# Random_Bit_Module.net
KiCad netlist of a schematic drawn in EAGLE
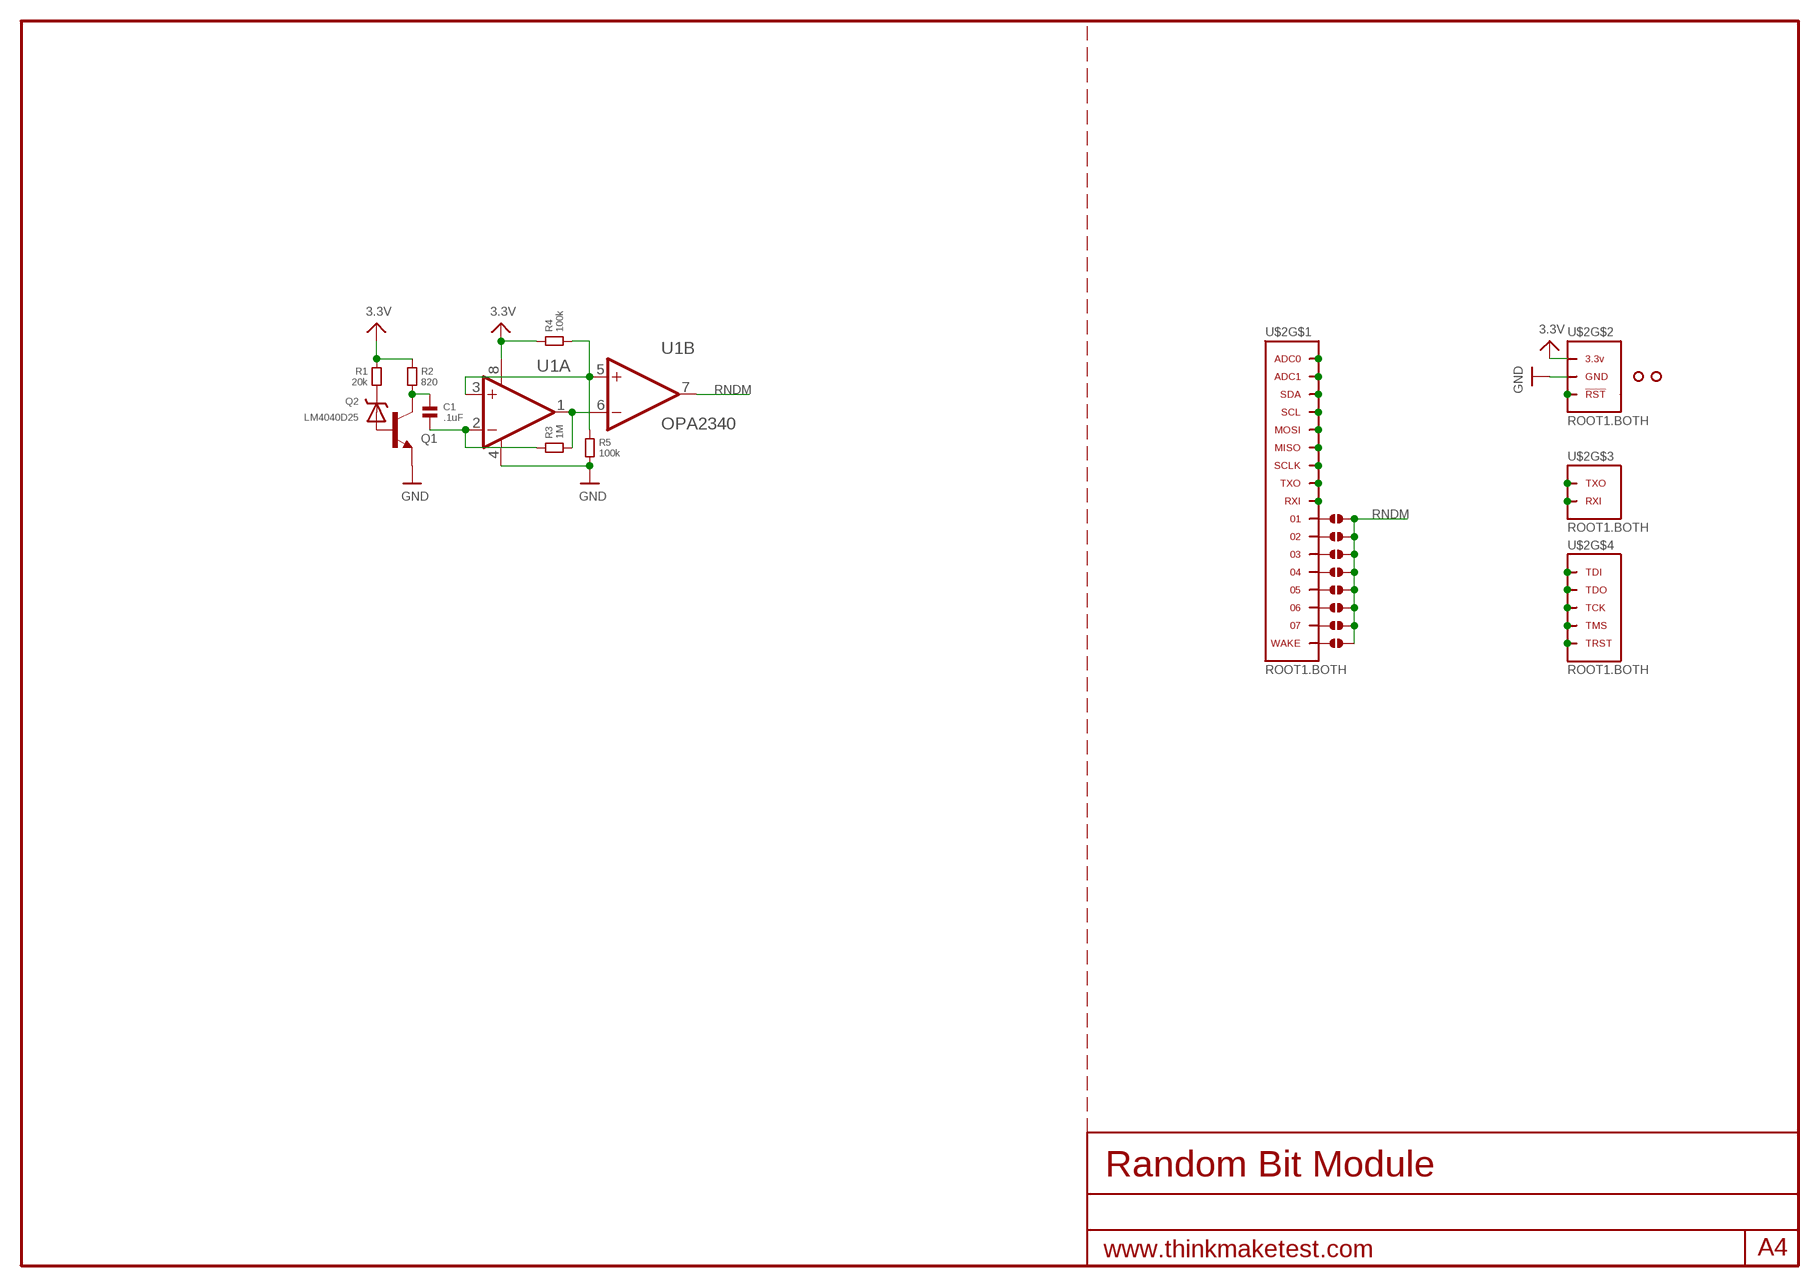
[diagram p0: schematic, sheet 1]

(export (version "E")
  (design (tool "Eeschema 10.0.6"))
  (components
    (comp (ref "C1")
      (value ".1uF")
      (footprint "eagle-import:0603")
      (libsource (lib "eagle-import") (part "CAPACITOR.0603"))
    )
    (comp (ref "J1")
      (value "SOLDERJUMPER.2.SML")
      (footprint "eagle-import:2.SML")
      (libsource (lib "eagle-import") (part "SOLDERJUMPER.2.SML"))
    )
    (comp (ref "J2")
      (value "SOLDERJUMPER.2.SML")
      (footprint "eagle-import:2.SML")
      (libsource (lib "eagle-import") (part "SOLDERJUMPER.2.SML"))
    )
    (comp (ref "J3")
      (value "SOLDERJUMPER.2.SML")
      (footprint "eagle-import:2.SML")
      (libsource (lib "eagle-import") (part "SOLDERJUMPER.2.SML"))
    )
    (comp (ref "J4")
      (value "SOLDERJUMPER.2.SML")
      (footprint "eagle-import:2.SML")
      (libsource (lib "eagle-import") (part "SOLDERJUMPER.2.SML"))
    )
    (comp (ref "J5")
      (value "SOLDERJUMPER.2.SML")
      (footprint "eagle-import:2.SML")
      (libsource (lib "eagle-import") (part "SOLDERJUMPER.2.SML"))
    )
    (comp (ref "J6")
      (value "SOLDERJUMPER.2.SML")
      (footprint "eagle-import:2.SML")
      (libsource (lib "eagle-import") (part "SOLDERJUMPER.2.SML"))
    )
    (comp (ref "J7")
      (value "SOLDERJUMPER.2.SML")
      (footprint "eagle-import:2.SML")
      (libsource (lib "eagle-import") (part "SOLDERJUMPER.2.SML"))
    )
    (comp (ref "J8")
      (value "SOLDERJUMPER.2.SML")
      (footprint "eagle-import:2.SML")
      (libsource (lib "eagle-import") (part "SOLDERJUMPER.2.SML"))
    )
    (comp (ref "Q1")
      (value "TRANSISTOR_NPN")
      (footprint "eagle-import:SOT23-R")
      (libsource (lib "eagle-import") (part "TRANSISTOR_NPN"))
    )
    (comp (ref "Q2")
      (value "LM4040D25")
      (footprint "eagle-import:SOT23-3")
      (libsource (lib "eagle-import") (part "V-REFERENCESMD"))
    )
    (comp (ref "R1")
      (value "20k")
      (footprint "eagle-import:0603")
      (libsource (lib "eagle-import") (part "RESISTOR.0603"))
    )
    (comp (ref "R2")
      (value "820")
      (footprint "eagle-import:0603")
      (libsource (lib "eagle-import") (part "RESISTOR.0603"))
    )
    (comp (ref "R3")
      (value "1M")
      (footprint "eagle-import:0603")
      (libsource (lib "eagle-import") (part "RESISTOR.0603"))
    )
    (comp (ref "R4")
      (value "100k")
      (footprint "eagle-import:0603")
      (libsource (lib "eagle-import") (part "RESISTOR.0603"))
    )
    (comp (ref "R5")
      (value "100k")
      (footprint "eagle-import:0603")
      (libsource (lib "eagle-import") (part "RESISTOR.0603"))
    )
    (comp (ref "U$2")
      (value "ROOT1.BOTH")
      (footprint "eagle-import:ROOT1.BOTH")
      (libsource (lib "eagle-import") (part "ROOT1.BOTH"))
    )
    (comp (ref "U$3")
      (value "HOLE.2MM")
      (footprint "eagle-import:2MM")
      (libsource (lib "eagle-import") (part "HOLE.2MM"))
    )
    (comp (ref "U$4")
      (value "HOLE.2MM")
      (footprint "eagle-import:2MM")
      (libsource (lib "eagle-import") (part "HOLE.2MM"))
    )
    (comp (ref "U1")
      (value "OPA2340")
      (footprint "eagle-import:MSOP08")
      (fields
        (field (name "MF") "TEXAS INSTRUMENTS")
        (field (name "MPN") "OPA2340EA/250")
        (field (name "MF_1") "TEXAS INSTRUMENTS")
        (field (name "MPN_1") "OPA2340UA")
        (field (name "OC_FARNELL") "1101541")
        (field (name "OC_NEWARK") "36K7581")
      )
      (libsource (lib "eagle-import") (part "OPA2340E"))
    )
  )
  (nets
    (net (code "1") (name "/RNDM") (class "Default")
      (node (ref "J1") (pin "2") (pinfunction "2_2") (pintype "bidirectional"))
      (node (ref "J2") (pin "2") (pinfunction "2_2") (pintype "bidirectional"))
      (node (ref "J3") (pin "2") (pinfunction "2_2") (pintype "bidirectional"))
      (node (ref "J4") (pin "2") (pinfunction "2_2") (pintype "bidirectional"))
      (node (ref "J5") (pin "2") (pinfunction "2_2") (pintype "bidirectional"))
      (node (ref "J6") (pin "2") (pinfunction "2_2") (pintype "bidirectional"))
      (node (ref "J7") (pin "2") (pinfunction "2_2") (pintype "bidirectional"))
      (node (ref "J8") (pin "2") (pinfunction "2_2") (pintype "bidirectional"))
      (node (ref "U1") (pin "7") (pinfunction "OUT_7") (pintype "output"))
    )
    (net (code "2") (name "3.3V") (class "Default")
      (node (ref "R1") (pin "1") (pinfunction "1_1") (pintype "bidirectional"))
      (node (ref "R2") (pin "1") (pinfunction "1_1") (pintype "bidirectional"))
      (node (ref "R4") (pin "1") (pinfunction "1_1") (pintype "bidirectional"))
      (node (ref "U$2") (pin "3.3V@1") (pinfunction "3.3V_3.3V@1") (pintype "bidirectional"))
      (node (ref "U$2") (pin "3.3V@10") (pinfunction "3.3V_3.3V@10") (pintype "bidirectional"))
      (node (ref "U$2") (pin "3.3V@11") (pinfunction "3.3V_3.3V@11") (pintype "bidirectional"))
      (node (ref "U$2") (pin "3.3V@12") (pinfunction "3.3V_3.3V@12") (pintype "bidirectional"))
      (node (ref "U$2") (pin "3.3V@13") (pinfunction "3.3V_3.3V@13") (pintype "bidirectional"))
      (node (ref "U$2") (pin "3.3V@14") (pinfunction "3.3V_3.3V@14") (pintype "bidirectional"))
      (node (ref "U$2") (pin "3.3V@15") (pinfunction "3.3V_3.3V@15") (pintype "bidirectional"))
      (node (ref "U$2") (pin "3.3V@16") (pinfunction "3.3V_3.3V@16") (pintype "bidirectional"))
      (node (ref "U$2") (pin "3.3V@17") (pinfunction "3.3V_3.3V@17") (pintype "bidirectional"))
      (node (ref "U$2") (pin "3.3V@18") (pinfunction "3.3V_3.3V@18") (pintype "bidirectional"))
      (node (ref "U$2") (pin "3.3V@19") (pinfunction "3.3V_3.3V@19") (pintype "bidirectional"))
      (node (ref "U$2") (pin "3.3V@2") (pinfunction "3.3V_3.3V@2") (pintype "bidirectional"))
      (node (ref "U$2") (pin "3.3V@20") (pinfunction "3.3V_3.3V@20") (pintype "bidirectional"))
      (node (ref "U$2") (pin "3.3V@21") (pinfunction "3.3V_3.3V@21") (pintype "bidirectional"))
      (node (ref "U$2") (pin "3.3V@22") (pinfunction "3.3V_3.3V@22") (pintype "bidirectional"))
      (node (ref "U$2") (pin "3.3V@23") (pinfunction "3.3V_3.3V@23") (pintype "bidirectional"))
      (node (ref "U$2") (pin "3.3V@24") (pinfunction "3.3V_3.3V@24") (pintype "bidirectional"))
      (node (ref "U$2") (pin "3.3V@3") (pinfunction "3.3V_3.3V@3") (pintype "bidirectional"))
      (node (ref "U$2") (pin "3.3V@4") (pinfunction "3.3V_3.3V@4") (pintype "bidirectional"))
      (node (ref "U$2") (pin "3.3V@5") (pinfunction "3.3V_3.3V@5") (pintype "bidirectional"))
      (node (ref "U$2") (pin "3.3V@6") (pinfunction "3.3V_3.3V@6") (pintype "bidirectional"))
      (node (ref "U$2") (pin "3.3V@7") (pinfunction "3.3V_3.3V@7") (pintype "bidirectional"))
      (node (ref "U$2") (pin "3.3V@8") (pinfunction "3.3V_3.3V@8") (pintype "bidirectional"))
      (node (ref "U$2") (pin "3.3V@9") (pinfunction "3.3V_3.3V@9") (pintype "bidirectional"))
      (node (ref "U$2") (pin "3.3V@VIA") (pinfunction "3.3V_3.3V@VIA") (pintype "bidirectional"))
      (node (ref "U1") (pin "8") (pinfunction "V+_8") (pintype "power_in"))
    )
    (net (code "3") (name "GND") (class "Default")
      (node (ref "Q1") (pin "2") (pinfunction "E_2") (pintype "passive"))
      (node (ref "R5") (pin "2") (pinfunction "2_2") (pintype "bidirectional"))
      (node (ref "U$2") (pin "GND@1") (pinfunction "GND_GND@1") (pintype "bidirectional"))
      (node (ref "U$2") (pin "GND@10") (pinfunction "GND_GND@10") (pintype "bidirectional"))
      (node (ref "U$2") (pin "GND@11") (pinfunction "GND_GND@11") (pintype "bidirectional"))
      (node (ref "U$2") (pin "GND@12") (pinfunction "GND_GND@12") (pintype "bidirectional"))
      (node (ref "U$2") (pin "GND@13") (pinfunction "GND_GND@13") (pintype "bidirectional"))
      (node (ref "U$2") (pin "GND@14") (pinfunction "GND_GND@14") (pintype "bidirectional"))
      (node (ref "U$2") (pin "GND@15") (pinfunction "GND_GND@15") (pintype "bidirectional"))
      (node (ref "U$2") (pin "GND@16") (pinfunction "GND_GND@16") (pintype "bidirectional"))
      (node (ref "U$2") (pin "GND@17") (pinfunction "GND_GND@17") (pintype "bidirectional"))
      (node (ref "U$2") (pin "GND@18") (pinfunction "GND_GND@18") (pintype "bidirectional"))
      (node (ref "U$2") (pin "GND@19") (pinfunction "GND_GND@19") (pintype "bidirectional"))
      (node (ref "U$2") (pin "GND@2") (pinfunction "GND_GND@2") (pintype "bidirectional"))
      (node (ref "U$2") (pin "GND@20") (pinfunction "GND_GND@20") (pintype "bidirectional"))
      (node (ref "U$2") (pin "GND@21") (pinfunction "GND_GND@21") (pintype "bidirectional"))
      (node (ref "U$2") (pin "GND@22") (pinfunction "GND_GND@22") (pintype "bidirectional"))
      (node (ref "U$2") (pin "GND@23") (pinfunction "GND_GND@23") (pintype "bidirectional"))
      (node (ref "U$2") (pin "GND@24") (pinfunction "GND_GND@24") (pintype "bidirectional"))
      (node (ref "U$2") (pin "GND@25") (pinfunction "GND_GND@25") (pintype "bidirectional"))
      (node (ref "U$2") (pin "GND@26") (pinfunction "GND_GND@26") (pintype "bidirectional"))
      (node (ref "U$2") (pin "GND@3") (pinfunction "GND_GND@3") (pintype "bidirectional"))
      (node (ref "U$2") (pin "GND@4") (pinfunction "GND_GND@4") (pintype "bidirectional"))
      (node (ref "U$2") (pin "GND@5") (pinfunction "GND_GND@5") (pintype "bidirectional"))
      (node (ref "U$2") (pin "GND@6") (pinfunction "GND_GND@6") (pintype "bidirectional"))
      (node (ref "U$2") (pin "GND@7") (pinfunction "GND_GND@7") (pintype "bidirectional"))
      (node (ref "U$2") (pin "GND@8") (pinfunction "GND_GND@8") (pintype "bidirectional"))
      (node (ref "U$2") (pin "GND@9") (pinfunction "GND_GND@9") (pintype "bidirectional"))
      (node (ref "U$2") (pin "GND@VIA") (pinfunction "GND_GND@VIA") (pintype "bidirectional"))
      (node (ref "U1") (pin "4") (pinfunction "V-_4") (pintype "power_in"))
    )
    (net (code "4") (name "Net-(J1-Pad1)") (class "Default")
      (node (ref "J1") (pin "1") (pinfunction "1_1") (pintype "bidirectional"))
      (node (ref "U$2") (pin "01") (pinfunction "01_01") (pintype "bidirectional"))
      (node (ref "U$2") (pin "01@1") (pinfunction "01_01@1") (pintype "bidirectional"))
      (node (ref "U$2") (pin "01@VIA") (pinfunction "01_01@VIA") (pintype "bidirectional"))
    )
    (net (code "5") (name "Net-(J2-Pad1)") (class "Default")
      (node (ref "J2") (pin "1") (pinfunction "1_1") (pintype "bidirectional"))
      (node (ref "U$2") (pin "02") (pinfunction "02_02") (pintype "bidirectional"))
      (node (ref "U$2") (pin "02@1") (pinfunction "02_02@1") (pintype "bidirectional"))
      (node (ref "U$2") (pin "02@VIA") (pinfunction "02_02@VIA") (pintype "bidirectional"))
    )
    (net (code "6") (name "Net-(J3-Pad1)") (class "Default")
      (node (ref "J3") (pin "1") (pinfunction "1_1") (pintype "bidirectional"))
      (node (ref "U$2") (pin "03") (pinfunction "03_03") (pintype "bidirectional"))
      (node (ref "U$2") (pin "03@1") (pinfunction "03_03@1") (pintype "bidirectional"))
      (node (ref "U$2") (pin "03@VIA") (pinfunction "03_03@VIA") (pintype "bidirectional"))
    )
    (net (code "7") (name "Net-(J4-Pad1)") (class "Default")
      (node (ref "J4") (pin "1") (pinfunction "1_1") (pintype "bidirectional"))
      (node (ref "U$2") (pin "04") (pinfunction "04_04") (pintype "bidirectional"))
      (node (ref "U$2") (pin "04@1") (pinfunction "04_04@1") (pintype "bidirectional"))
      (node (ref "U$2") (pin "04@VIA") (pinfunction "04_04@VIA") (pintype "bidirectional"))
    )
    (net (code "8") (name "Net-(J5-Pad1)") (class "Default")
      (node (ref "J5") (pin "1") (pinfunction "1_1") (pintype "bidirectional"))
      (node (ref "U$2") (pin "05") (pinfunction "05_05") (pintype "bidirectional"))
      (node (ref "U$2") (pin "05@1") (pinfunction "05_05@1") (pintype "bidirectional"))
      (node (ref "U$2") (pin "05@VIA") (pinfunction "05_05@VIA") (pintype "bidirectional"))
    )
    (net (code "9") (name "Net-(J6-Pad1)") (class "Default")
      (node (ref "J6") (pin "1") (pinfunction "1_1") (pintype "bidirectional"))
      (node (ref "U$2") (pin "06") (pinfunction "06_06") (pintype "bidirectional"))
      (node (ref "U$2") (pin "06@1") (pinfunction "06_06@1") (pintype "bidirectional"))
      (node (ref "U$2") (pin "06@VIA") (pinfunction "06_06@VIA") (pintype "bidirectional"))
    )
    (net (code "10") (name "Net-(J7-Pad1)") (class "Default")
      (node (ref "J7") (pin "1") (pinfunction "1_1") (pintype "bidirectional"))
      (node (ref "U$2") (pin "07") (pinfunction "07_07") (pintype "bidirectional"))
      (node (ref "U$2") (pin "07@1") (pinfunction "07_07@1") (pintype "bidirectional"))
      (node (ref "U$2") (pin "07@VIA") (pinfunction "07_07@VIA") (pintype "bidirectional"))
    )
    (net (code "11") (name "Net-(J8-Pad1)") (class "Default")
      (node (ref "J8") (pin "1") (pinfunction "1_1") (pintype "bidirectional"))
      (node (ref "U$2") (pin "WAKE") (pinfunction "WAKE_WAKE") (pintype "bidirectional"))
      (node (ref "U$2") (pin "WAKE@1") (pinfunction "WAKE_WAKE@1") (pintype "bidirectional"))
      (node (ref "U$2") (pin "WAKE@VIA") (pinfunction "WAKE_WAKE@VIA") (pintype "bidirectional"))
    )
    (net (code "12") (name "Net-(Q1-B)") (class "Default")
      (node (ref "Q1") (pin "1") (pinfunction "B_1") (pintype "passive"))
      (node (ref "Q2") (pin "2") (pinfunction "A_2") (pintype "passive"))
    )
    (net (code "13") (name "Net-(Q1-C)") (class "Default")
      (node (ref "C1") (pin "1") (pinfunction "1_1") (pintype "bidirectional"))
      (node (ref "Q1") (pin "3") (pinfunction "C_3") (pintype "passive"))
      (node (ref "R2") (pin "2") (pinfunction "2_2") (pintype "bidirectional"))
    )
    (net (code "14") (name "Net-(Q2-C)") (class "Default")
      (node (ref "Q2") (pin "1") (pinfunction "C_1") (pintype "passive"))
      (node (ref "R1") (pin "2") (pinfunction "2_2") (pintype "bidirectional"))
    )
    (net (code "15") (name "Net-(U$2-PadADC0)") (class "Default")
      (node (ref "U$2") (pin "ADC0") (pinfunction "ADC0_ADC0") (pintype "bidirectional"))
      (node (ref "U$2") (pin "ADC0@1") (pinfunction "ADC0_ADC0@1") (pintype "bidirectional"))
      (node (ref "U$2") (pin "ADC0@VIA") (pinfunction "ADC0_ADC0@VIA") (pintype "bidirectional"))
    )
    (net (code "16") (name "Net-(U$2-PadADC1)") (class "Default")
      (node (ref "U$2") (pin "ADC1") (pinfunction "ADC1_ADC1") (pintype "bidirectional"))
      (node (ref "U$2") (pin "ADC1@1") (pinfunction "ADC1_ADC1@1") (pintype "bidirectional"))
      (node (ref "U$2") (pin "ADC1@VIA") (pinfunction "ADC1_ADC1@VIA") (pintype "bidirectional"))
    )
    (net (code "17") (name "Net-(U$2-PadMISO)") (class "Default")
      (node (ref "U$2") (pin "MISO") (pinfunction "MISO_MISO") (pintype "bidirectional"))
      (node (ref "U$2") (pin "MISO@1") (pinfunction "MISO_MISO@1") (pintype "bidirectional"))
      (node (ref "U$2") (pin "MISO@VIA") (pinfunction "MISO_MISO@VIA") (pintype "bidirectional"))
    )
    (net (code "18") (name "Net-(U$2-PadMOSI)") (class "Default")
      (node (ref "U$2") (pin "MOSI") (pinfunction "MOSI_MOSI") (pintype "bidirectional"))
      (node (ref "U$2") (pin "MOSI@1") (pinfunction "MOSI_MOSI@1") (pintype "bidirectional"))
      (node (ref "U$2") (pin "MOSI@VIA") (pinfunction "MOSI_MOSI@VIA") (pintype "bidirectional"))
    )
    (net (code "19") (name "Net-(U$2-PadRXI)") (class "Default")
      (node (ref "U$2") (pin "RXI") (pinfunction "RXI_RXI") (pintype "bidirectional"))
      (node (ref "U$2") (pin "RXI@1") (pinfunction "RXI_RXI@1") (pintype "bidirectional"))
      (node (ref "U$2") (pin "RXI@VIA") (pinfunction "RXI_RXI@VIA") (pintype "bidirectional"))
    )
    (net (code "20") (name "Net-(U$2-PadSCL)") (class "Default")
      (node (ref "U$2") (pin "SCL") (pinfunction "SCL_SCL") (pintype "bidirectional"))
      (node (ref "U$2") (pin "SCL@1") (pinfunction "SCL_SCL@1") (pintype "bidirectional"))
      (node (ref "U$2") (pin "SCL@VIA") (pinfunction "SCL_SCL@VIA") (pintype "bidirectional"))
    )
    (net (code "21") (name "Net-(U$2-PadSCLK)") (class "Default")
      (node (ref "U$2") (pin "SCLK") (pinfunction "SCLK_SCLK") (pintype "bidirectional"))
      (node (ref "U$2") (pin "SCLK@1") (pinfunction "SCLK_SCLK@1") (pintype "bidirectional"))
      (node (ref "U$2") (pin "SCLK@VIA") (pinfunction "SCLK_SCLK@VIA") (pintype "bidirectional"))
    )
    (net (code "22") (name "Net-(U$2-PadSDA)") (class "Default")
      (node (ref "U$2") (pin "SDA") (pinfunction "SDA_SDA") (pintype "bidirectional"))
      (node (ref "U$2") (pin "SDA@1") (pinfunction "SDA_SDA@1") (pintype "bidirectional"))
      (node (ref "U$2") (pin "SDA@VIA") (pinfunction "SDA_SDA@VIA") (pintype "bidirectional"))
    )
    (net (code "23") (name "Net-(U$2-PadTCK)") (class "Default")
      (node (ref "U$2") (pin "TCK") (pinfunction "TCK_TCK") (pintype "bidirectional"))
      (node (ref "U$2") (pin "TCK@1") (pinfunction "TCK_TCK@1") (pintype "bidirectional"))
      (node (ref "U$2") (pin "TCK@VIA") (pinfunction "TCK_TCK@VIA") (pintype "bidirectional"))
    )
    (net (code "24") (name "Net-(U$2-PadTDI)") (class "Default")
      (node (ref "U$2") (pin "TDI") (pinfunction "TDI_TDI") (pintype "bidirectional"))
      (node (ref "U$2") (pin "TDI@1") (pinfunction "TDI_TDI@1") (pintype "bidirectional"))
      (node (ref "U$2") (pin "TDI@VIA") (pinfunction "TDI_TDI@VIA") (pintype "bidirectional"))
    )
    (net (code "25") (name "Net-(U$2-PadTDO)") (class "Default")
      (node (ref "U$2") (pin "TDO") (pinfunction "TDO_TDO") (pintype "bidirectional"))
      (node (ref "U$2") (pin "TDO@1") (pinfunction "TDO_TDO@1") (pintype "bidirectional"))
      (node (ref "U$2") (pin "TDO@VIA") (pinfunction "TDO_TDO@VIA") (pintype "bidirectional"))
    )
    (net (code "26") (name "Net-(U$2-PadTMS)") (class "Default")
      (node (ref "U$2") (pin "TMS") (pinfunction "TMS_TMS") (pintype "bidirectional"))
      (node (ref "U$2") (pin "TMS@1") (pinfunction "TMS_TMS@1") (pintype "bidirectional"))
      (node (ref "U$2") (pin "TMS@VIA") (pinfunction "TMS_TMS@VIA") (pintype "bidirectional"))
    )
    (net (code "27") (name "Net-(U$2-PadTRST)") (class "Default")
      (node (ref "U$2") (pin "TRST") (pinfunction "TRST_TRST") (pintype "bidirectional"))
      (node (ref "U$2") (pin "TRST@1") (pinfunction "TRST_TRST@1") (pintype "bidirectional"))
      (node (ref "U$2") (pin "TRST@VIA") (pinfunction "TRST_TRST@VIA") (pintype "bidirectional"))
    )
    (net (code "28") (name "Net-(U$2-PadTXO)") (class "Default")
      (node (ref "U$2") (pin "TXO") (pinfunction "TXO_TXO") (pintype "bidirectional"))
      (node (ref "U$2") (pin "TXO@1") (pinfunction "TXO_TXO@1") (pintype "bidirectional"))
      (node (ref "U$2") (pin "TXO@VIA") (pinfunction "TXO_TXO@VIA") (pintype "bidirectional"))
    )
    (net (code "29") (name "Net-(U$2B-~{RST}-PadRST)") (class "Default")
      (node (ref "U$2") (pin "RST") (pinfunction "~{RST}_RST") (pintype "bidirectional"))
      (node (ref "U$2") (pin "RST@1") (pinfunction "~{RST}_RST@1") (pintype "bidirectional"))
      (node (ref "U$2") (pin "RST@VIA") (pinfunction "~{RST}_RST@VIA") (pintype "bidirectional"))
    )
    (net (code "30") (name "Net-(U$2C-RXI-PadRXI.DBG)") (class "Default")
      (node (ref "U$2") (pin "RXI.DBG") (pinfunction "RXI_RXI.DBG") (pintype "bidirectional"))
      (node (ref "U$2") (pin "RXI.DBG@1") (pinfunction "RXI_RXI.DBG@1") (pintype "bidirectional"))
      (node (ref "U$2") (pin "RXI.DBG@VIA") (pinfunction "RXI_RXI.DBG@VIA") (pintype "bidirectional"))
    )
    (net (code "31") (name "Net-(U$2C-TXO-PadTXO.DBG)") (class "Default")
      (node (ref "U$2") (pin "TXO.DBG") (pinfunction "TXO_TXO.DBG") (pintype "bidirectional"))
      (node (ref "U$2") (pin "TXO.DBG@1") (pinfunction "TXO_TXO.DBG@1") (pintype "bidirectional"))
      (node (ref "U$2") (pin "TXO.DBG@VIA") (pinfunction "TXO_TXO.DBG@VIA") (pintype "bidirectional"))
    )
    (net (code "32") (name "Net-(U1A-+IN)") (class "Default")
      (node (ref "R4") (pin "2") (pinfunction "2_2") (pintype "bidirectional"))
      (node (ref "R5") (pin "1") (pinfunction "1_1") (pintype "bidirectional"))
      (node (ref "U1") (pin "3") (pinfunction "+IN_3") (pintype "input"))
      (node (ref "U1") (pin "5") (pinfunction "+IN_5") (pintype "input"))
    )
    (net (code "33") (name "Net-(U1A--IN)") (class "Default")
      (node (ref "C1") (pin "2") (pinfunction "2_2") (pintype "bidirectional"))
      (node (ref "R3") (pin "1") (pinfunction "1_1") (pintype "bidirectional"))
      (node (ref "U1") (pin "2") (pinfunction "-IN_2") (pintype "input"))
    )
    (net (code "34") (name "Net-(U1A-OUT)") (class "Default")
      (node (ref "R3") (pin "2") (pinfunction "2_2") (pintype "bidirectional"))
      (node (ref "U1") (pin "1") (pinfunction "OUT_1") (pintype "output"))
      (node (ref "U1") (pin "6") (pinfunction "-IN_6") (pintype "input"))
    )
  )
)
